# Optocoupler.net
KiCad netlist of a schematic drawn in Altium Designer
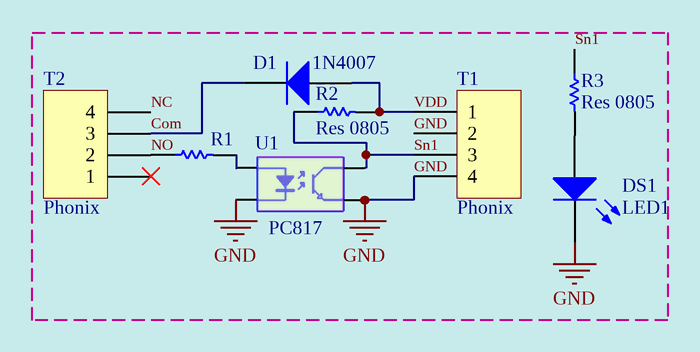
[diagram p0: Optocoupler.SchDoc]

(export (version "E")
  (design (tool "Eeschema 10.0.6"))
  (components
    (comp (ref "D1") (value "1N4007") (footprint "Diod") (libsource (lib "PMLIB") (part "Diode")))
    (comp (ref "DS1") (value "LED1") (footprint "LED1") (libsource (lib "PMLIB") (part "LED1")))
    (comp (ref "R1") (value "Res 0805") (footprint "R0805") (libsource (lib "PMLIB") (part "Res 0805")))
    (comp (ref "R2") (value "Res 0805") (footprint "R0805") (libsource (lib "PMLIB") (part "Res 0805")))
    (comp (ref "R3") (value "Res 0805") (footprint "R0805") (libsource (lib "PMLIB") (part "Res 0805")))
    (comp (ref "T1") (value "Phonix") (footprint "Phonix-4") (libsource (lib "") (part "Phonix-4_1")))
    (comp (ref "T2") (value "Phonix") (footprint "Phonix-4") (libsource (lib "PMLIB") (part "Phonix-4")))
    (comp (ref "U1")
      (value "PC817")
      (footprint "OptoCupler")
      (libsource (lib "PMLIB") (part "Optoisolator(smd)"))
    )
  )
  (nets
    (net (code "1") (name "/Com") (class "Default")
      (node (ref "D1") (pin "K") (pinfunction "K_K") (pintype "passive"))
      (node (ref "T2") (pin "3") (pinfunction "3_3") (pintype "passive"))
    )
    (net (code "2") (name "/NC") (class "Default")
      (node (ref "T2") (pin "4") (pinfunction "4_4") (pintype "passive"))
    )
    (net (code "3") (name "/NO") (class "Default")
      (node (ref "R1") (pin "2") (pinfunction "2_2") (pintype "passive"))
      (node (ref "T2") (pin "2") (pinfunction "2_2") (pintype "passive"))
    )
    (net (code "4") (name "/Sn1") (class "Default")
      (node (ref "R2") (pin "2") (pinfunction "2_2") (pintype "passive"))
      (node (ref "R3") (pin "2") (pinfunction "2_2") (pintype "passive"))
      (node (ref "T1") (pin "3") (pinfunction "3_3") (pintype "passive"))
      (node (ref "U1") (pin "4") (pinfunction "C_4") (pintype "passive"))
    )
    (net (code "5") (name "/VDD") (class "Default")
      (node (ref "D1") (pin "A") (pinfunction "A_A") (pintype "passive"))
      (node (ref "R2") (pin "1") (pinfunction "1_1") (pintype "passive"))
      (node (ref "T1") (pin "1") (pinfunction "1_1") (pintype "passive"))
    )
    (net (code "6") (name "GND") (class "Default")
      (node (ref "DS1") (pin "K") (pinfunction "K_K") (pintype "passive"))
      (node (ref "T1") (pin "2") (pinfunction "2_2") (pintype "passive"))
      (node (ref "T1") (pin "4") (pinfunction "4_4") (pintype "passive"))
      (node (ref "U1") (pin "2") (pinfunction "K_2") (pintype "passive"))
      (node (ref "U1") (pin "3") (pinfunction "E_3") (pintype "passive"))
    )
    (net (code "7") (name "Net-(DS1-PadA)") (class "Default")
      (node (ref "DS1") (pin "A") (pinfunction "A_A") (pintype "passive"))
      (node (ref "R3") (pin "1") (pinfunction "1_1") (pintype "passive"))
    )
    (net (code "8") (name "Net-(U1-A)") (class "Default")
      (node (ref "R1") (pin "1") (pinfunction "1_1") (pintype "passive"))
      (node (ref "U1") (pin "1") (pinfunction "A_1") (pintype "passive"))
    )
    (net (code "9") (name "unconnected-(T2-Pad1)") (class "Default")
      (node (ref "T2") (pin "1") (pinfunction "1_1") (pintype "passive+no_connect"))
    )
  )
)
